# ESQUEMATICO.net
KiCad netlist of a schematic drawn in Altium Designer
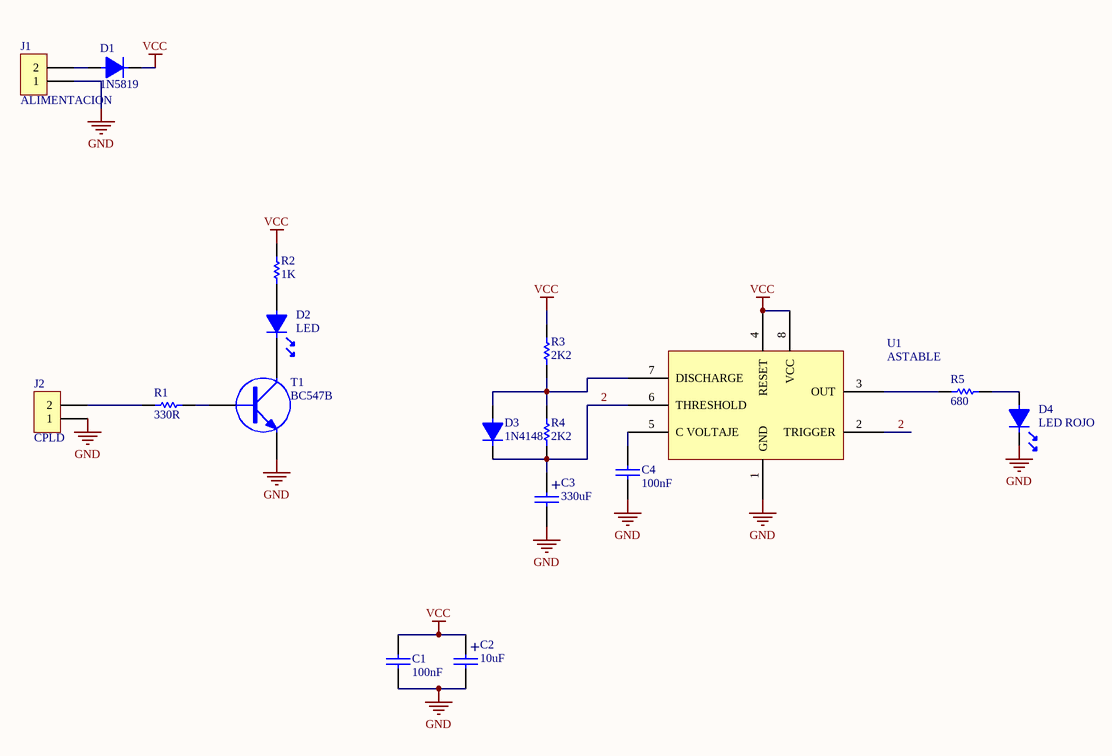
[diagram p0: ESQUEMATICO.SchDoc]

(export (version "E")
  (design (tool "Eeschema 10.0.6"))
  (components
    (comp (ref "C1") (value "100nF") (footprint "CAP200") (libsource (lib "LIBEBAL") (part "CAP")))
    (comp (ref "C2") (value "10uF") (footprint "CAP100RP") (libsource (lib "LIBEBAL") (part "CAPPOL")))
    (comp (ref "C3") (value "330uF") (footprint "CAP200RP") (libsource (lib "LIBEBAL") (part "CAPPOL")))
    (comp (ref "C4") (value "100nF") (footprint "CAP200") (libsource (lib "LIBEBAL") (part "CAP")))
    (comp (ref "D1") (value "1N5819") (footprint "DO41") (libsource (lib "LIBEBAL") (part "DIODO")))
    (comp (ref "D2") (value "LED") (footprint "LED3") (libsource (lib "LIBEBAL") (part "LED")))
    (comp (ref "D3") (value "1N4148") (footprint "DO41") (libsource (lib "LIBEBAL") (part "DIODO")))
    (comp (ref "D4") (value "LED ROJO") (footprint "LED3") (libsource (lib "LIBEBAL") (part "LED")))
    (comp (ref "J1")
      (value "ALIMENTACION")
      (footprint "BORNERA2")
      (libsource (lib "LIBEBAL") (part "BORNERA 2"))
    )
    (comp (ref "J2") (value "CPLD") (footprint "BORNERA2") (libsource (lib "LIBEBAL") (part "BORNERA 2")))
    (comp (ref "R1") (value "330R") (footprint "RES400") (libsource (lib "LIBEBAL") (part "RES")))
    (comp (ref "R2") (value "1K") (footprint "RES400") (libsource (lib "LIBEBAL") (part "RES")))
    (comp (ref "R3") (value "2K2") (footprint "RES400") (libsource (lib "LIBEBAL") (part "RES")))
    (comp (ref "R4") (value "2K2") (footprint "RES400") (libsource (lib "LIBEBAL") (part "RES")))
    (comp (ref "R5") (value "680") (footprint "RES400") (libsource (lib "LIBEBAL") (part "RES")))
    (comp (ref "T1") (value "BC547B") (footprint "TO92") (libsource (lib "LIBEBAL") (part "TRANSISTOR NPN")))
    (comp (ref "U1")
      (value "ASTABLE")
      (footprint "DIP8")
      (description "Timer")
      (libsource (lib "LIBEBAL") (part "LM555"))
    )
  )
  (nets
    (net (code "1") (name "/2") (class "Default")
      (node (ref "C3") (pin "1") (pinfunction "1_1") (pintype "passive"))
      (node (ref "D3") (pin "2") (pinfunction "2_2") (pintype "passive"))
      (node (ref "R4") (pin "1") (pinfunction "1_1") (pintype "passive"))
      (node (ref "U1") (pin "2") (pinfunction "TRIGGER_2") (pintype "passive"))
      (node (ref "U1") (pin "6") (pinfunction "THRESHOLD_6") (pintype "passive"))
    )
    (net (code "2") (name "GND") (class "Default")
      (node (ref "C1") (pin "2") (pinfunction "2_2") (pintype "passive"))
      (node (ref "C2") (pin "2") (pinfunction "2_2") (pintype "passive"))
      (node (ref "C3") (pin "2") (pinfunction "2_2") (pintype "passive"))
      (node (ref "C4") (pin "2") (pinfunction "2_2") (pintype "passive"))
      (node (ref "D4") (pin "2") (pinfunction "2_2") (pintype "passive"))
      (node (ref "J1") (pin "1") (pinfunction "1_1") (pintype "passive"))
      (node (ref "J2") (pin "1") (pinfunction "1_1") (pintype "passive"))
      (node (ref "T1") (pin "3") (pinfunction "E_3") (pintype "passive"))
      (node (ref "U1") (pin "1") (pinfunction "GND_1") (pintype "passive"))
    )
    (net (code "3") (name "Net-(D1-Pad1)") (class "Default")
      (node (ref "D1") (pin "1") (pinfunction "1_1") (pintype "passive"))
      (node (ref "J1") (pin "2") (pinfunction "2_2") (pintype "passive"))
    )
    (net (code "4") (name "Net-(D2-Pad1)") (class "Default")
      (node (ref "D2") (pin "1") (pinfunction "1_1") (pintype "passive"))
      (node (ref "R2") (pin "1") (pinfunction "1_1") (pintype "passive"))
    )
    (net (code "5") (name "Net-(D4-Pad1)") (class "Default")
      (node (ref "D4") (pin "1") (pinfunction "1_1") (pintype "passive"))
      (node (ref "R5") (pin "2") (pinfunction "2_2") (pintype "passive"))
    )
    (net (code "6") (name "Net-(J2-Pad2)") (class "Default")
      (node (ref "J2") (pin "2") (pinfunction "2_2") (pintype "passive"))
      (node (ref "R1") (pin "2") (pinfunction "2_2") (pintype "passive"))
    )
    (net (code "7") (name "Net-(T1-B)") (class "Default")
      (node (ref "R1") (pin "1") (pinfunction "1_1") (pintype "passive"))
      (node (ref "T1") (pin "1") (pinfunction "B_1") (pintype "passive"))
    )
    (net (code "8") (name "Net-(T1-C)") (class "Default")
      (node (ref "D2") (pin "2") (pinfunction "2_2") (pintype "passive"))
      (node (ref "T1") (pin "2") (pinfunction "C_2") (pintype "passive"))
    )
    (net (code "9") (name "Net-(U1-C_VOLTAJE)") (class "Default")
      (node (ref "C4") (pin "1") (pinfunction "1_1") (pintype "passive"))
      (node (ref "U1") (pin "5") (pinfunction "C_VOLTAJE_5") (pintype "passive"))
    )
    (net (code "10") (name "Net-(U1-DISCHARGE)") (class "Default")
      (node (ref "D3") (pin "1") (pinfunction "1_1") (pintype "passive"))
      (node (ref "R3") (pin "1") (pinfunction "1_1") (pintype "passive"))
      (node (ref "R4") (pin "2") (pinfunction "2_2") (pintype "passive"))
      (node (ref "U1") (pin "7") (pinfunction "DISCHARGE_7") (pintype "passive"))
    )
    (net (code "11") (name "Net-(U1-OUT)") (class "Default")
      (node (ref "R5") (pin "1") (pinfunction "1_1") (pintype "passive"))
      (node (ref "U1") (pin "3") (pinfunction "OUT_3") (pintype "passive"))
    )
    (net (code "12") (name "VCC") (class "Default")
      (node (ref "C1") (pin "1") (pinfunction "1_1") (pintype "passive"))
      (node (ref "C2") (pin "1") (pinfunction "1_1") (pintype "passive"))
      (node (ref "D1") (pin "2") (pinfunction "2_2") (pintype "passive"))
      (node (ref "R2") (pin "2") (pinfunction "2_2") (pintype "passive"))
      (node (ref "R3") (pin "2") (pinfunction "2_2") (pintype "passive"))
      (node (ref "U1") (pin "4") (pinfunction "RESET_4") (pintype "passive"))
      (node (ref "U1") (pin "8") (pinfunction "VCC_8") (pintype "passive"))
    )
  )
)
